# 4Show_CE.net
KiCad netlist of a schematic drawn in EAGLE
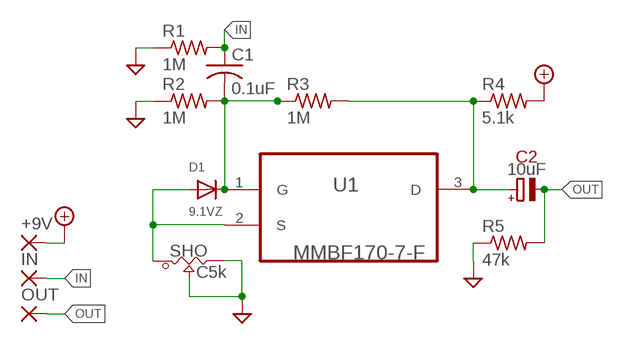
[diagram p0: schematic, sheet 1]

(export (version "E")
  (design (tool "Eeschema 10.0.6"))
  (components
    (comp (ref "+9V")
      (value "SMD2")
      (footprint "eagle-import:SMD1,27-2,54")
      (libsource (lib "eagle-import") (part "SMD2"))
    )
    (comp (ref "C1")
      (value "0.1uF")
      (footprint "eagle-import:C0603")
      (libsource (lib "eagle-import") (part "C-USC0603"))
    )
    (comp (ref "C2")
      (value "10uF")
      (footprint "eagle-import:PAN_B")
      (libsource (lib "eagle-import") (part "PAN_B"))
    )
    (comp (ref "D1")
      (value "9.1VZ")
      (footprint "eagle-import:SOD-123")
      (libsource (lib "eagle-import") (part "DIODESOD-123"))
    )
    (comp (ref "IN")
      (value "SMD2")
      (footprint "eagle-import:SMD1,27-2,54")
      (libsource (lib "eagle-import") (part "SMD2"))
    )
    (comp (ref "OUT")
      (value "SMD2")
      (footprint "eagle-import:SMD1,27-2,54")
      (libsource (lib "eagle-import") (part "SMD2"))
    )
    (comp (ref "R1")
      (value "1M")
      (footprint "eagle-import:R0603")
      (libsource (lib "eagle-import") (part "R-US_R0603"))
    )
    (comp (ref "R2")
      (value "1M")
      (footprint "eagle-import:R0603")
      (libsource (lib "eagle-import") (part "R-US_R0603"))
    )
    (comp (ref "R3")
      (value "1M")
      (footprint "eagle-import:R0603")
      (libsource (lib "eagle-import") (part "R-US_R0603"))
    )
    (comp (ref "R4")
      (value "5.1k")
      (footprint "eagle-import:R0603")
      (libsource (lib "eagle-import") (part "R-US_R0603"))
    )
    (comp (ref "R5")
      (value "47k")
      (footprint "eagle-import:R0603")
      (libsource (lib "eagle-import") (part "R-US_R0603"))
    )
    (comp (ref "SHO")
      (value "C5k")
      (footprint "eagle-import:POT_9MM_SMD")
      (libsource (lib "eagle-import") (part "POT_9MM_SMD"))
    )
    (comp (ref "U1")
      (value "MMBF170-7-F")
      (footprint "eagle-import:SOT103P240X110-3N")
      (fields (field (name "MF") "Diodes Inc."))
      (libsource (lib "eagle-import") (part "MMBF170-7-F"))
    )
  )
  (nets
    (net (code "1") (name "+9V") (class "Default")
      (node (ref "+9V") (pin "1") (pinfunction "P_1") (pintype "passive"))
      (node (ref "R4") (pin "2") (pinfunction "2_2") (pintype "passive"))
    )
    (net (code "2") (name "GND") (class "Default")
      (node (ref "R1") (pin "1") (pinfunction "1_1") (pintype "passive"))
      (node (ref "R2") (pin "1") (pinfunction "1_1") (pintype "passive"))
      (node (ref "R5") (pin "1") (pinfunction "1_1") (pintype "passive"))
      (node (ref "SHO") (pin "2") (pinfunction "2_2") (pintype "bidirectional"))
      (node (ref "SHO") (pin "3") (pinfunction "3_3") (pintype "bidirectional"))
    )
    (net (code "3") (name "IN") (class "Default")
      (node (ref "C1") (pin "1") (pinfunction "1_1") (pintype "passive"))
      (node (ref "IN") (pin "1") (pinfunction "P_1") (pintype "passive"))
      (node (ref "R1") (pin "2") (pinfunction "2_2") (pintype "passive"))
    )
    (net (code "4") (name "Net-(C2-+)") (class "Default")
      (node (ref "C2") (pin "1+") (pinfunction "+_1+") (pintype "passive"))
      (node (ref "R3") (pin "2") (pinfunction "2_2") (pintype "passive"))
      (node (ref "R4") (pin "1") (pinfunction "1_1") (pintype "passive"))
      (node (ref "U1") (pin "3") (pinfunction "D_3") (pintype "output"))
    )
    (net (code "5") (name "Net-(U1-G)") (class "Default")
      (node (ref "C1") (pin "2") (pinfunction "2_2") (pintype "passive"))
      (node (ref "D1") (pin "C") (pinfunction "C_C") (pintype "passive"))
      (node (ref "R2") (pin "2") (pinfunction "2_2") (pintype "passive"))
      (node (ref "R3") (pin "1") (pinfunction "1_1") (pintype "passive"))
      (node (ref "U1") (pin "1") (pinfunction "G_1") (pintype "input"))
    )
    (net (code "6") (name "Net-(U1-S)") (class "Default")
      (node (ref "D1") (pin "A") (pinfunction "A_A") (pintype "passive"))
      (node (ref "SHO") (pin "1") (pinfunction "1_1") (pintype "bidirectional"))
      (node (ref "U1") (pin "2") (pinfunction "S_2") (pintype "passive"))
    )
    (net (code "7") (name "OUT") (class "Default")
      (node (ref "C2") (pin "2-") (pinfunction "-_2-") (pintype "passive"))
      (node (ref "OUT") (pin "1") (pinfunction "P_1") (pintype "passive"))
      (node (ref "R5") (pin "2") (pinfunction "2_2") (pintype "passive"))
    )
  )
)
